# Heater.net
KiCad netlist of a schematic drawn in Altium Designer
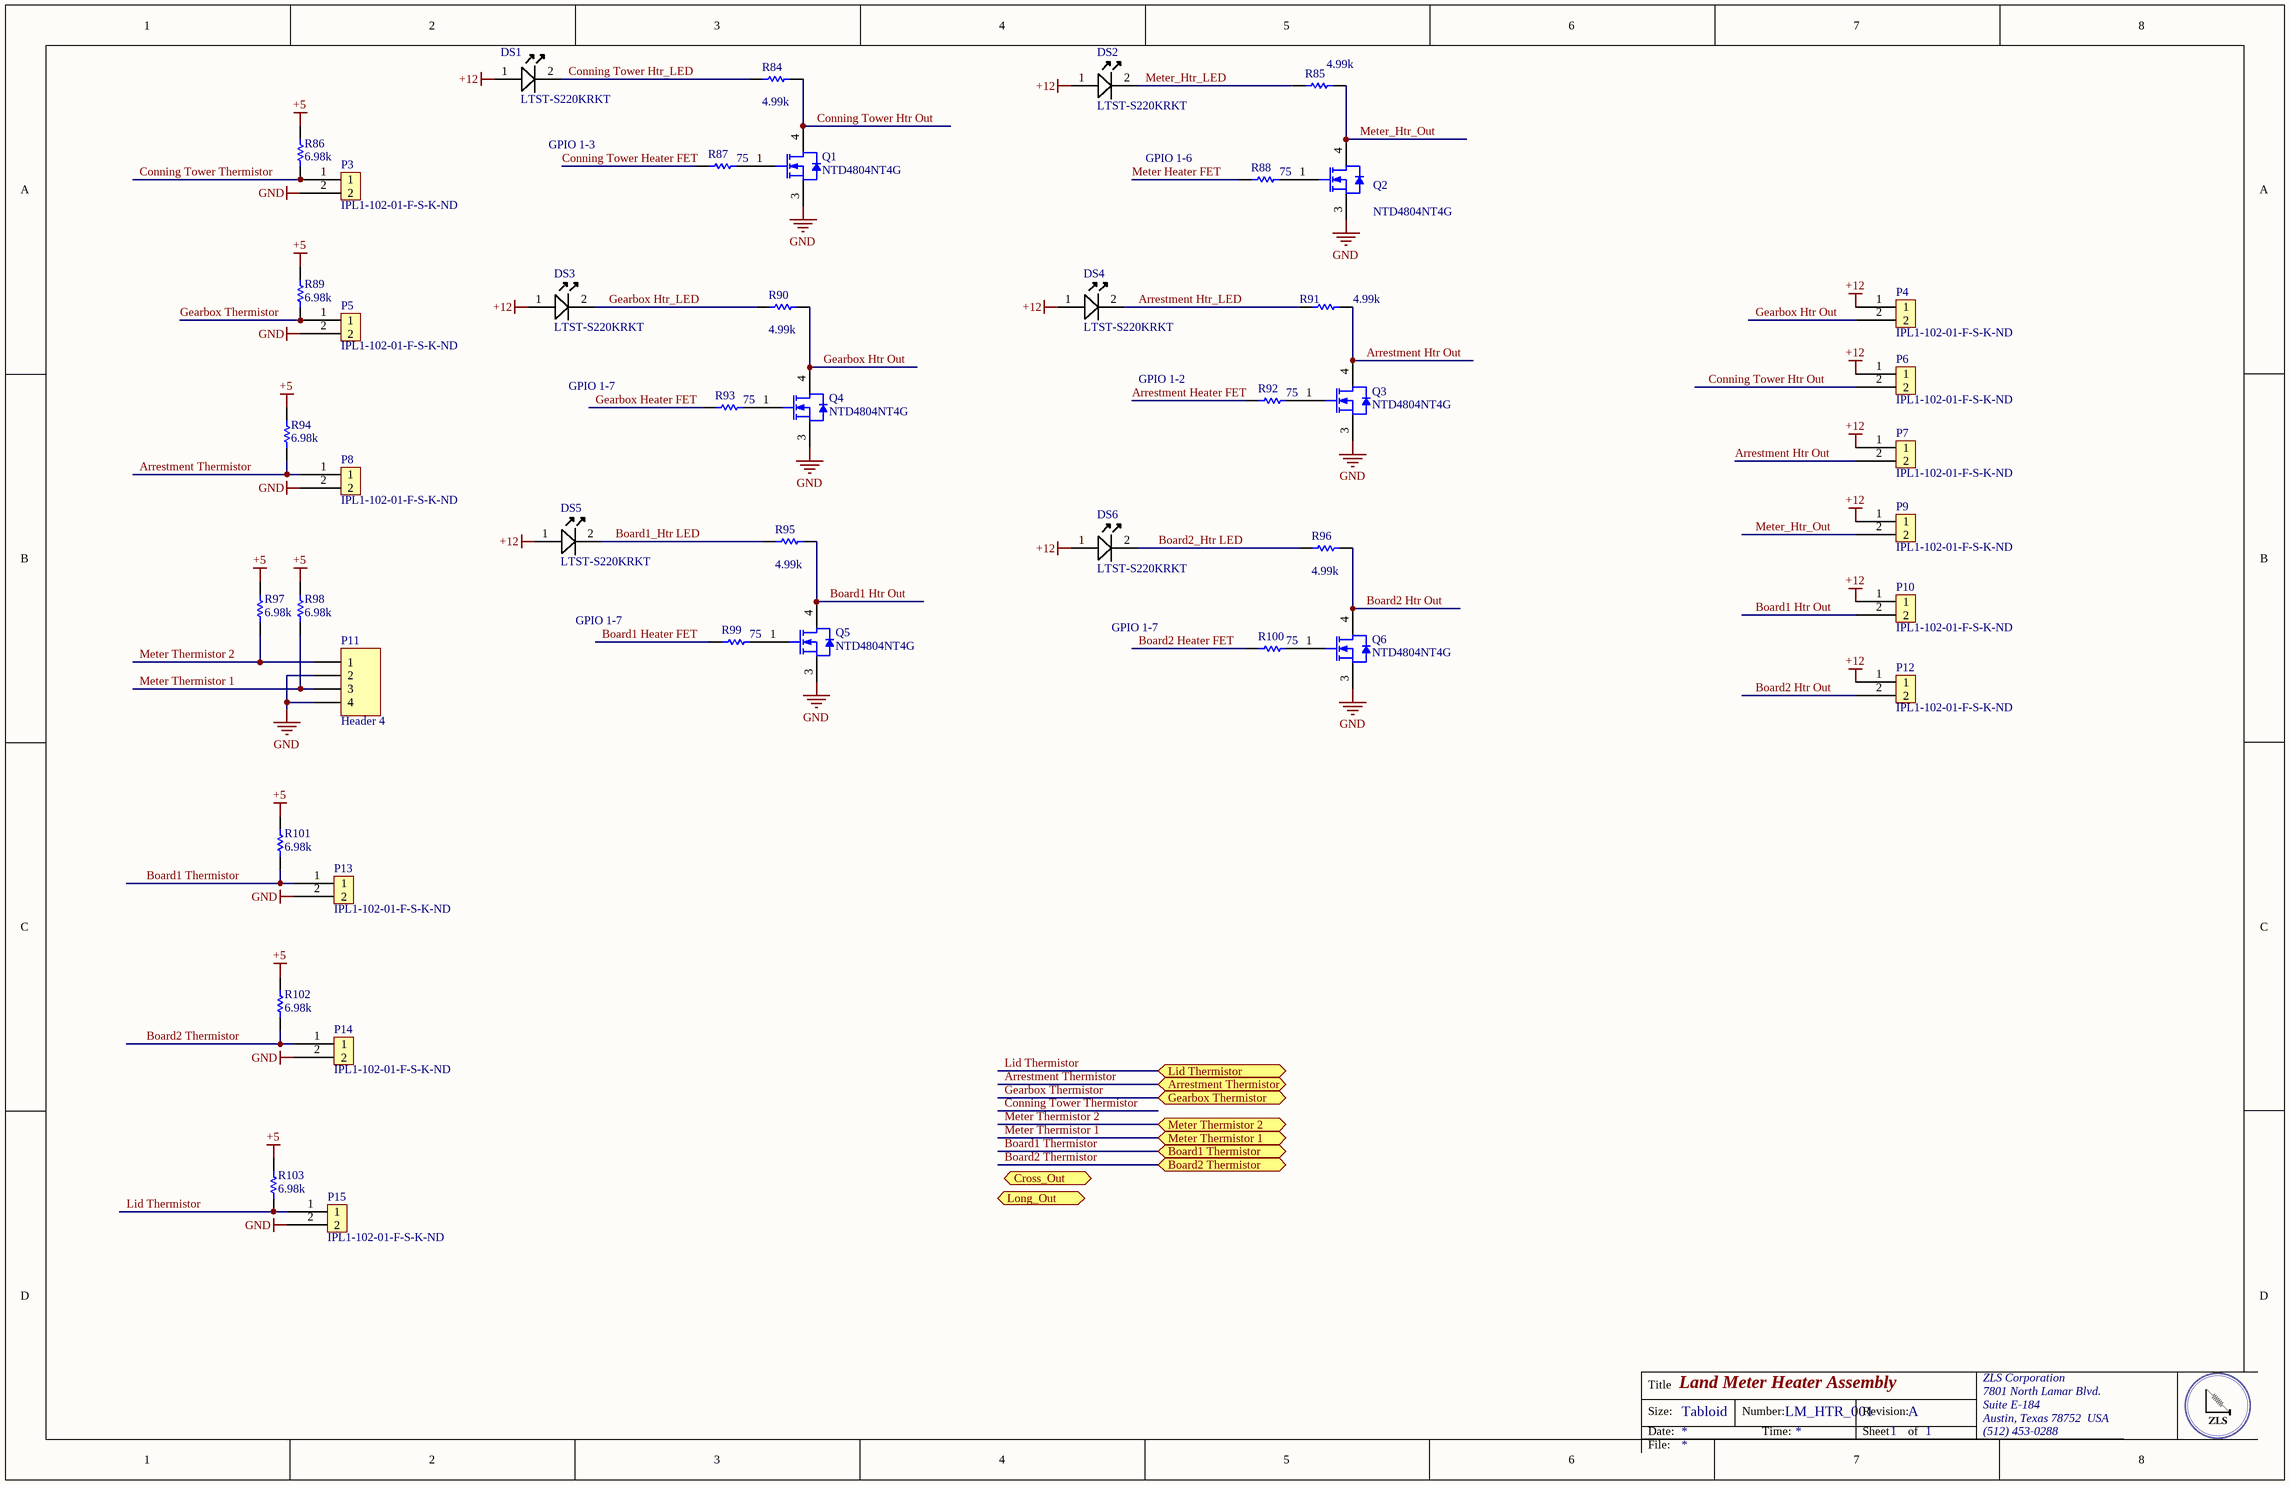
[diagram p0: Heater.SchDoc]

(export (version "E")
  (design (tool "Eeschema 10.0.6"))
  (components
    (comp (ref "DS1")
      (value "Visible Name Value Type    False Description Lite-On LTST-S220KRKT Red LED, 631 nm 2012 (0805) Side View, Rectangle Lens SMD package STRING")
      (footprint "0805C_L")
      (fields
        (field (name "MANUFACTURER") "Vishay / Lite-On")
        (field (name "MANUFACTURER PART NUMBER") "LTST-S220KRKT")
      )
      (libsource (lib "*") (part "LED A/K"))
    )
    (comp (ref "DS2")
      (value "Visible Name Value Type    False Description Lite-On LTST-S220KRKT Red LED, 631 nm 2012 (0805) Side View, Rectangle Lens SMD package STRING")
      (footprint "0805C_L")
      (fields
        (field (name "MANUFACTURER") "Vishay / Lite-On")
        (field (name "MANUFACTURER PART NUMBER") "LTST-S220KRKT")
      )
      (libsource (lib "*") (part "LED A/K"))
    )
    (comp (ref "DS3")
      (value "Visible Name Value Type    False Description Lite-On LTST-S220KRKT Red LED, 631 nm 2012 (0805) Side View, Rectangle Lens SMD package STRING")
      (footprint "0805C_L")
      (fields
        (field (name "MANUFACTURER") "Vishay / Lite-On")
        (field (name "MANUFACTURER PART NUMBER") "LTST-S220KRKT")
      )
      (libsource (lib "*") (part "LED A/K"))
    )
    (comp (ref "DS4")
      (value "Visible Name Value Type    False Description Lite-On LTST-S220KRKT Red LED, 631 nm 2012 (0805) Side View, Rectangle Lens SMD package STRING")
      (footprint "0805C_L")
      (fields
        (field (name "MANUFACTURER") "Vishay / Lite-On")
        (field (name "MANUFACTURER PART NUMBER") "LTST-S220KRKT")
      )
      (libsource (lib "*") (part "LED A/K"))
    )
    (comp (ref "DS5")
      (value "Visible Name Value Type    False Description Lite-On LTST-S220KRKT Red LED, 631 nm 2012 (0805) Side View, Rectangle Lens SMD package STRING")
      (footprint "0805C_L")
      (fields
        (field (name "MANUFACTURER") "Vishay / Lite-On")
        (field (name "MANUFACTURER PART NUMBER") "LTST-S220KRKT")
      )
      (libsource (lib "*") (part "LED A/K"))
    )
    (comp (ref "DS6")
      (value "Visible Name Value Type    False Description Lite-On LTST-S220KRKT Red LED, 631 nm 2012 (0805) Side View, Rectangle Lens SMD package STRING")
      (footprint "0805C_L")
      (fields
        (field (name "MANUFACTURER") "Vishay / Lite-On")
        (field (name "MANUFACTURER PART NUMBER") "LTST-S220KRKT")
      )
      (libsource (lib "*") (part "LED A/K"))
    )
    (comp (ref "P3")
      (value "IPL1-102-01-F-S-K")
      (footprint "IPL1-102-01-F-S-K")
      (description ".100 TERMINAL ASSEMBLY")
      (fields
        (field (name "SUPPLIER PART NUMBER 1") "IPL1-102-01-F-S-K-ND")
        (field (name "MANUFACTURER") "Samtec Inc.")
      )
      (libsource (lib "ZLS_Schematic_lib") (part "IPL1-102-01-F-S-K"))
    )
    (comp (ref "P4")
      (value "IPL1-102-01-F-S-K")
      (footprint "IPL1-102-01-F-S-K")
      (description ".100 TERMINAL ASSEMBLY")
      (fields
        (field (name "SUPPLIER PART NUMBER 1") "IPL1-102-01-F-S-K-ND")
        (field (name "MANUFACTURER") "Samtec Inc.")
      )
      (libsource (lib "ZLS_Schematic_lib") (part "IPL1-102-01-F-S-K"))
    )
    (comp (ref "P5")
      (value "IPL1-102-01-F-S-K")
      (footprint "IPL1-102-01-F-S-K")
      (description ".100 TERMINAL ASSEMBLY")
      (fields
        (field (name "SUPPLIER PART NUMBER 1") "IPL1-102-01-F-S-K-ND")
        (field (name "MANUFACTURER") "Samtec Inc.")
      )
      (libsource (lib "ZLS_Schematic_lib") (part "IPL1-102-01-F-S-K"))
    )
    (comp (ref "P6")
      (value "IPL1-102-01-F-S-K")
      (footprint "IPL1-102-01-F-S-K")
      (description ".100 TERMINAL ASSEMBLY")
      (fields
        (field (name "SUPPLIER PART NUMBER 1") "IPL1-102-01-F-S-K-ND")
        (field (name "MANUFACTURER") "Samtec Inc.")
      )
      (libsource (lib "ZLS_Schematic_lib") (part "IPL1-102-01-F-S-K"))
    )
    (comp (ref "P7")
      (value "IPL1-102-01-F-S-K")
      (footprint "IPL1-102-01-F-S-K")
      (description ".100 TERMINAL ASSEMBLY")
      (fields
        (field (name "SUPPLIER PART NUMBER 1") "IPL1-102-01-F-S-K-ND")
        (field (name "MANUFACTURER") "Samtec Inc.")
      )
      (libsource (lib "ZLS_Schematic_lib") (part "IPL1-102-01-F-S-K"))
    )
    (comp (ref "P8")
      (value "IPL1-102-01-F-S-K")
      (footprint "IPL1-102-01-F-S-K")
      (description ".100 TERMINAL ASSEMBLY")
      (fields
        (field (name "SUPPLIER PART NUMBER 1") "IPL1-102-01-F-S-K-ND")
        (field (name "MANUFACTURER") "Samtec Inc.")
      )
      (libsource (lib "ZLS_Schematic_lib") (part "IPL1-102-01-F-S-K"))
    )
    (comp (ref "P9")
      (value "IPL1-102-01-F-S-K")
      (footprint "IPL1-102-01-F-S-K")
      (description ".100 TERMINAL ASSEMBLY")
      (fields
        (field (name "SUPPLIER PART NUMBER 1") "IPL1-102-01-F-S-K-ND")
        (field (name "MANUFACTURER") "Samtec Inc.")
      )
      (libsource (lib "ZLS_Schematic_lib") (part "IPL1-102-01-F-S-K"))
    )
    (comp (ref "P10")
      (value "IPL1-102-01-F-S-K")
      (footprint "IPL1-102-01-F-S-K")
      (description ".100 TERMINAL ASSEMBLY")
      (fields
        (field (name "SUPPLIER PART NUMBER 1") "IPL1-102-01-F-S-K-ND")
        (field (name "MANUFACTURER") "Samtec Inc.")
      )
      (libsource (lib "ZLS_Schematic_lib") (part "IPL1-102-01-F-S-K"))
    )
    (comp (ref "P11")
      (value "Header 4")
      (footprint "IPL1-104-01-L-S-K")
      (description "Header, 4-Pin")
      (fields (field (name "PUBLISHER") "Altium Limited"))
      (libsource (lib "Miscellaneous Connectors") (part "Header 4"))
    )
    (comp (ref "P12")
      (value "IPL1-102-01-F-S-K")
      (footprint "IPL1-102-01-F-S-K")
      (description ".100 TERMINAL ASSEMBLY")
      (fields
        (field (name "SUPPLIER PART NUMBER 1") "IPL1-102-01-F-S-K-ND")
        (field (name "MANUFACTURER") "Samtec Inc.")
      )
      (libsource (lib "ZLS_Schematic_lib") (part "IPL1-102-01-F-S-K"))
    )
    (comp (ref "P13")
      (value "IPL1-102-01-F-S-K")
      (footprint "IPL1-102-01-F-S-K")
      (description ".100 TERMINAL ASSEMBLY")
      (fields
        (field (name "SUPPLIER PART NUMBER 1") "IPL1-102-01-F-S-K-ND")
        (field (name "MANUFACTURER") "Samtec Inc.")
      )
      (libsource (lib "ZLS_Schematic_lib") (part "IPL1-102-01-F-S-K"))
    )
    (comp (ref "P14")
      (value "IPL1-102-01-F-S-K")
      (footprint "IPL1-102-01-F-S-K")
      (description ".100 TERMINAL ASSEMBLY")
      (fields
        (field (name "SUPPLIER PART NUMBER 1") "IPL1-102-01-F-S-K-ND")
        (field (name "MANUFACTURER") "Samtec Inc.")
      )
      (libsource (lib "ZLS_Schematic_lib") (part "IPL1-102-01-F-S-K"))
    )
    (comp (ref "P15")
      (value "IPL1-102-01-F-S-K")
      (footprint "IPL1-102-01-F-S-K")
      (description ".100 TERMINAL ASSEMBLY")
      (fields
        (field (name "SUPPLIER PART NUMBER 1") "IPL1-102-01-F-S-K-ND")
        (field (name "MANUFACTURER") "Samtec Inc.")
      )
      (libsource (lib "ZLS_Schematic_lib") (part "IPL1-102-01-F-S-K"))
    )
    (comp (ref "Q1")
      (value "NTD4804NT4G")
      (footprint "ONSC-DPAK-3-369AA-01_V")
      (description "Power MOSFET, 30 V, 117 A, Single N-Channel, 3-Pin DPAK, Pb-Free, Tape and Reel")
      (fields (field (name "MANUFACTURER") "On Semiconductor"))
      (libsource (lib "Altium Content Vault") (part "CMP-1058-00341-1"))
    )
    (comp (ref "Q2")
      (value "NTD4804NT4G")
      (footprint "ONSC-DPAK-3-369AA-01_V")
      (description "Power MOSFET, 30 V, 117 A, Single N-Channel, 3-Pin DPAK, Pb-Free, Tape and Reel")
      (fields (field (name "MANUFACTURER") "On Semiconductor"))
      (libsource (lib "Altium Content Vault") (part "CMP-1058-00341-1"))
    )
    (comp (ref "Q3")
      (value "NTD4804NT4G")
      (footprint "ONSC-DPAK-3-369AA-01_V")
      (description "Power MOSFET, 30 V, 117 A, Single N-Channel, 3-Pin DPAK, Pb-Free, Tape and Reel")
      (fields (field (name "MANUFACTURER") "On Semiconductor"))
      (libsource (lib "Altium Content Vault") (part "CMP-1058-00341-1"))
    )
    (comp (ref "Q4")
      (value "NTD4804NT4G")
      (footprint "ONSC-DPAK-3-369AA-01_V")
      (description "Power MOSFET, 30 V, 117 A, Single N-Channel, 3-Pin DPAK, Pb-Free, Tape and Reel")
      (fields (field (name "MANUFACTURER") "On Semiconductor"))
      (libsource (lib "Altium Content Vault") (part "CMP-1058-00341-1"))
    )
    (comp (ref "Q5")
      (value "NTD4804NT4G")
      (footprint "ONSC-DPAK-3-369AA-01_V")
      (description "Power MOSFET, 30 V, 117 A, Single N-Channel, 3-Pin DPAK, Pb-Free, Tape and Reel")
      (fields (field (name "MANUFACTURER") "On Semiconductor"))
      (libsource (lib "Altium Content Vault") (part "CMP-1058-00341-1"))
    )
    (comp (ref "Q6")
      (value "NTD4804NT4G")
      (footprint "ONSC-DPAK-3-369AA-01_V")
      (description "Power MOSFET, 30 V, 117 A, Single N-Channel, 3-Pin DPAK, Pb-Free, Tape and Reel")
      (fields (field (name "MANUFACTURER") "On Semiconductor"))
      (libsource (lib "Altium Content Vault") (part "CMP-1058-00341-1"))
    )
    (comp (ref "R84")
      (value "~")
      (footprint "RESC0805(2012)_L")
      (fields
        (field (name "MANUFACTURER") "Vishay Dale")
        (field (name "MANUFACTURER PART NUMBER") "CRCW08054K99FKEA")
        (field (name "RESISTANCE (OHMS)") "4.99k")
        (field (name "TOLERANCE") "±1%")
      )
      (libsource (lib "Altium Content Vault") (part "CMP-1013-00393-1"))
    )
    (comp (ref "R85")
      (value "~")
      (footprint "RESC0805(2012)_L")
      (fields
        (field (name "MANUFACTURER") "Vishay Dale")
        (field (name "MANUFACTURER PART NUMBER") "CRCW08054K99FKEA")
        (field (name "RESISTANCE (OHMS)") "4.99k")
        (field (name "TOLERANCE") "±1%")
      )
      (libsource (lib "Altium Content Vault") (part "CMP-1013-00393-1"))
    )
    (comp (ref "R86")
      (value "6K98 1% 0805(2012)")
      (footprint "RESC0805(2012)_N")
      (description "6K98 0.125W 1% 0805 (2012 Metric)  SMD")
      (fields
        (field (name "MANUFACTURER") "Vishay Dale")
        (field (name "MANUFACTURER PART NUMBER") "CRCW08056K98FKEA")
        (field (name "RESISTANCE (OHMS)") "6.98k")
      )
      (libsource (lib "Altium Content Vault") (part "CMP-1013-00606-1"))
    )
    (comp (ref "R87")
      (value "~")
      (footprint "RESC0805(2012)_L")
      (fields
        (field (name "MANUFACTURER") "Vishay Dale")
        (field (name "MANUFACTURER PART NUMBER") "CRCW080575R0FKEA")
        (field (name "RESISTANCE (OHMS)") "75")
        (field (name "TOLERANCE") "±1%")
      )
      (libsource (lib "Altium Content Vault") (part "CMP-1013-00393-1"))
    )
    (comp (ref "R88")
      (value "~")
      (footprint "RESC0805(2012)_L")
      (fields
        (field (name "MANUFACTURER") "Vishay Dale")
        (field (name "MANUFACTURER PART NUMBER") "CRCW080575R0FKEA")
        (field (name "RESISTANCE (OHMS)") "75")
        (field (name "TOLERANCE") "±1%")
      )
      (libsource (lib "Altium Content Vault") (part "CMP-1013-00393-1"))
    )
    (comp (ref "R89")
      (value "6K98 1% 0805(2012)")
      (footprint "RESC0805(2012)_N")
      (description "6K98 0.125W 1% 0805 (2012 Metric)  SMD")
      (fields
        (field (name "MANUFACTURER") "Vishay Dale")
        (field (name "MANUFACTURER PART NUMBER") "CRCW08056K98FKEA")
        (field (name "RESISTANCE (OHMS)") "6.98k")
      )
      (libsource (lib "Altium Content Vault") (part "CMP-1013-00606-1"))
    )
    (comp (ref "R90")
      (value "~")
      (footprint "RESC0805(2012)_L")
      (fields
        (field (name "MANUFACTURER") "Vishay Dale")
        (field (name "MANUFACTURER PART NUMBER") "CRCW08054K99FKEA")
        (field (name "RESISTANCE (OHMS)") "4.99k")
        (field (name "TOLERANCE") "±1%")
      )
      (libsource (lib "Altium Content Vault") (part "CMP-1013-00393-1"))
    )
    (comp (ref "R91")
      (value "~")
      (footprint "RESC0805(2012)_L")
      (fields
        (field (name "MANUFACTURER") "Vishay Dale")
        (field (name "MANUFACTURER PART NUMBER") "CRCW08054K99FKEA")
        (field (name "RESISTANCE (OHMS)") "4.99k")
        (field (name "TOLERANCE") "±1%")
      )
      (libsource (lib "Altium Content Vault") (part "CMP-1013-00393-1"))
    )
    (comp (ref "R92")
      (value "~")
      (footprint "RESC0805(2012)_L")
      (fields
        (field (name "MANUFACTURER") "Vishay Dale")
        (field (name "MANUFACTURER PART NUMBER") "CRCW080575R0FKEA")
        (field (name "RESISTANCE (OHMS)") "75")
        (field (name "TOLERANCE") "±1%")
      )
      (libsource (lib "Altium Content Vault") (part "CMP-1013-00393-1"))
    )
    (comp (ref "R93")
      (value "~")
      (footprint "RESC0805(2012)_L")
      (fields
        (field (name "MANUFACTURER") "Vishay Dale")
        (field (name "MANUFACTURER PART NUMBER") "CRCW080575R0FKEA")
        (field (name "RESISTANCE (OHMS)") "75")
        (field (name "TOLERANCE") "±1%")
      )
      (libsource (lib "Altium Content Vault") (part "CMP-1013-00393-1"))
    )
    (comp (ref "R94")
      (value "6K98 1% 0805(2012)")
      (footprint "RESC0805(2012)_N")
      (description "6K98 0.125W 1% 0805 (2012 Metric)  SMD")
      (fields
        (field (name "MANUFACTURER") "Vishay Dale")
        (field (name "MANUFACTURER PART NUMBER") "CRCW08056K98FKEA")
        (field (name "RESISTANCE (OHMS)") "6.98k")
      )
      (libsource (lib "Altium Content Vault") (part "CMP-1013-00606-1"))
    )
    (comp (ref "R95")
      (value "~")
      (footprint "RESC0805(2012)_L")
      (fields
        (field (name "MANUFACTURER") "Vishay Dale")
        (field (name "MANUFACTURER PART NUMBER") "CRCW08054K99FKEA")
        (field (name "RESISTANCE (OHMS)") "4.99k")
        (field (name "TOLERANCE") "±1%")
      )
      (libsource (lib "Altium Content Vault") (part "CMP-1013-00393-1"))
    )
    (comp (ref "R96")
      (value "~")
      (footprint "RESC0805(2012)_L")
      (fields
        (field (name "MANUFACTURER") "Vishay Dale")
        (field (name "MANUFACTURER PART NUMBER") "CRCW08054K99FKEA")
        (field (name "RESISTANCE (OHMS)") "4.99k")
        (field (name "TOLERANCE") "±1%")
      )
      (libsource (lib "Altium Content Vault") (part "CMP-1013-00393-1"))
    )
    (comp (ref "R97")
      (value "6K98 1% 0805(2012)")
      (footprint "RESC0805(2012)_N")
      (description "6K98 0.125W 1% 0805 (2012 Metric)  SMD")
      (fields
        (field (name "MANUFACTURER") "Vishay Dale")
        (field (name "MANUFACTURER PART NUMBER") "CRCW08056K98FKEA")
        (field (name "RESISTANCE (OHMS)") "6.98k")
      )
      (libsource (lib "Altium Content Vault") (part "CMP-1013-00606-1"))
    )
    (comp (ref "R98")
      (value "6K98 1% 0805(2012)")
      (footprint "RESC0805(2012)_N")
      (description "6K98 0.125W 1% 0805 (2012 Metric)  SMD")
      (fields
        (field (name "MANUFACTURER") "Vishay Dale")
        (field (name "MANUFACTURER PART NUMBER") "CRCW08056K98FKEA")
        (field (name "RESISTANCE (OHMS)") "6.98k")
      )
      (libsource (lib "Altium Content Vault") (part "CMP-1013-00606-1"))
    )
    (comp (ref "R99")
      (value "~")
      (footprint "RESC0805(2012)_L")
      (fields
        (field (name "MANUFACTURER") "Vishay Dale")
        (field (name "MANUFACTURER PART NUMBER") "CRCW080575R0FKEA")
        (field (name "RESISTANCE (OHMS)") "75")
        (field (name "TOLERANCE") "±1%")
      )
      (libsource (lib "Altium Content Vault") (part "CMP-1013-00393-1"))
    )
    (comp (ref "R100")
      (value "~")
      (footprint "RESC0805(2012)_L")
      (fields
        (field (name "MANUFACTURER") "Vishay Dale")
        (field (name "MANUFACTURER PART NUMBER") "CRCW080575R0FKEA")
        (field (name "RESISTANCE (OHMS)") "75")
        (field (name "TOLERANCE") "±1%")
      )
      (libsource (lib "Altium Content Vault") (part "CMP-1013-00393-1"))
    )
    (comp (ref "R101")
      (value "6K98 1% 0805(2012)")
      (footprint "RESC0805(2012)_N")
      (description "6K98 0.125W 1% 0805 (2012 Metric)  SMD")
      (fields
        (field (name "MANUFACTURER") "Vishay Dale")
        (field (name "MANUFACTURER PART NUMBER") "CRCW08056K98FKEA")
        (field (name "RESISTANCE (OHMS)") "6.98k")
      )
      (libsource (lib "Altium Content Vault") (part "CMP-1013-00606-1"))
    )
    (comp (ref "R102")
      (value "6K98 1% 0805(2012)")
      (footprint "RESC0805(2012)_N")
      (description "6K98 0.125W 1% 0805 (2012 Metric)  SMD")
      (fields
        (field (name "MANUFACTURER") "Vishay Dale")
        (field (name "MANUFACTURER PART NUMBER") "CRCW08056K98FKEA")
        (field (name "RESISTANCE (OHMS)") "6.98k")
      )
      (libsource (lib "Altium Content Vault") (part "CMP-1013-00606-1"))
    )
    (comp (ref "R103")
      (value "6K98 1% 0805(2012)")
      (footprint "RESC0805(2012)_N")
      (description "6K98 0.125W 1% 0805 (2012 Metric)  SMD")
      (fields
        (field (name "MANUFACTURER") "Vishay Dale")
        (field (name "MANUFACTURER PART NUMBER") "CRCW08056K98FKEA")
        (field (name "RESISTANCE (OHMS)") "6.98k")
      )
      (libsource (lib "Altium Content Vault") (part "CMP-1013-00606-1"))
    )
  )
  (nets
    (net (code "1") (name "+5") (class "Default")
      (node (ref "R101") (pin "1") (pinfunction "1_1") (pintype "passive"))
      (node (ref "R102") (pin "1") (pinfunction "1_1") (pintype "passive"))
      (node (ref "R103") (pin "1") (pinfunction "1_1") (pintype "passive"))
      (node (ref "R86") (pin "2") (pinfunction "2_2") (pintype "passive"))
      (node (ref "R89") (pin "2") (pinfunction "2_2") (pintype "passive"))
      (node (ref "R94") (pin "1") (pinfunction "1_1") (pintype "passive"))
      (node (ref "R97") (pin "1") (pinfunction "1_1") (pintype "passive"))
      (node (ref "R98") (pin "2") (pinfunction "2_2") (pintype "passive"))
    )
    (net (code "2") (name "+12") (class "Default")
      (node (ref "DS1") (pin "1") (pinfunction "A_1") (pintype "passive"))
      (node (ref "DS2") (pin "1") (pinfunction "A_1") (pintype "passive"))
      (node (ref "DS3") (pin "1") (pinfunction "A_1") (pintype "passive"))
      (node (ref "DS4") (pin "1") (pinfunction "A_1") (pintype "passive"))
      (node (ref "DS5") (pin "1") (pinfunction "A_1") (pintype "passive"))
      (node (ref "DS6") (pin "1") (pinfunction "A_1") (pintype "passive"))
      (node (ref "P10") (pin "1") (pinfunction "1_1") (pintype "passive"))
      (node (ref "P12") (pin "1") (pinfunction "1_1") (pintype "passive"))
      (node (ref "P4") (pin "1") (pinfunction "1_1") (pintype "passive"))
      (node (ref "P6") (pin "1") (pinfunction "1_1") (pintype "passive"))
      (node (ref "P7") (pin "1") (pinfunction "1_1") (pintype "passive"))
      (node (ref "P9") (pin "1") (pinfunction "1_1") (pintype "passive"))
    )
    (net (code "3") (name "/Arrestment Heater FET") (class "Default")
      (node (ref "R92") (pin "1") (pinfunction "1_1") (pintype "passive"))
    )
    (net (code "4") (name "/Arrestment Htr Out") (class "Default")
      (node (ref "P7") (pin "2") (pinfunction "2_2") (pintype "passive"))
      (node (ref "Q3") (pin "4") (pinfunction "D_4") (pintype "passive"))
      (node (ref "R91") (pin "2") (pinfunction "2_2") (pintype "passive"))
    )
    (net (code "5") (name "/Arrestment Htr_LED") (class "Default")
      (node (ref "DS4") (pin "2") (pinfunction "K_2") (pintype "passive"))
      (node (ref "R91") (pin "1") (pinfunction "1_1") (pintype "passive"))
    )
    (net (code "6") (name "/Arrestment Thermistor") (class "Default")
      (node (ref "P8") (pin "1") (pinfunction "1_1") (pintype "passive"))
      (node (ref "R94") (pin "2") (pinfunction "2_2") (pintype "passive"))
    )
    (net (code "7") (name "/Board1 Heater FET") (class "Default")
      (node (ref "R99") (pin "1") (pinfunction "1_1") (pintype "passive"))
    )
    (net (code "8") (name "/Board1 Htr Out") (class "Default")
      (node (ref "P10") (pin "2") (pinfunction "2_2") (pintype "passive"))
      (node (ref "Q5") (pin "4") (pinfunction "D_4") (pintype "passive"))
      (node (ref "R95") (pin "1") (pinfunction "1_1") (pintype "passive"))
    )
    (net (code "9") (name "/Board1 Thermistor") (class "Default")
      (node (ref "P13") (pin "1") (pinfunction "1_1") (pintype "passive"))
      (node (ref "R101") (pin "2") (pinfunction "2_2") (pintype "passive"))
    )
    (net (code "10") (name "/Board1_Htr LED") (class "Default")
      (node (ref "DS5") (pin "2") (pinfunction "K_2") (pintype "passive"))
      (node (ref "R95") (pin "2") (pinfunction "2_2") (pintype "passive"))
    )
    (net (code "11") (name "/Board2 Heater FET") (class "Default")
      (node (ref "R100") (pin "1") (pinfunction "1_1") (pintype "passive"))
    )
    (net (code "12") (name "/Board2 Htr Out") (class "Default")
      (node (ref "P12") (pin "2") (pinfunction "2_2") (pintype "passive"))
      (node (ref "Q6") (pin "4") (pinfunction "D_4") (pintype "passive"))
      (node (ref "R96") (pin "1") (pinfunction "1_1") (pintype "passive"))
    )
    (net (code "13") (name "/Board2 Thermistor") (class "Default")
      (node (ref "P14") (pin "1") (pinfunction "1_1") (pintype "passive"))
      (node (ref "R102") (pin "2") (pinfunction "2_2") (pintype "passive"))
    )
    (net (code "14") (name "/Board2_Htr LED") (class "Default")
      (node (ref "DS6") (pin "2") (pinfunction "K_2") (pintype "passive"))
      (node (ref "R96") (pin "2") (pinfunction "2_2") (pintype "passive"))
    )
    (net (code "15") (name "/Conning Tower Heater FET") (class "Default")
      (node (ref "R87") (pin "1") (pinfunction "1_1") (pintype "passive"))
    )
    (net (code "16") (name "/Conning Tower Htr Out") (class "Default")
      (node (ref "P6") (pin "2") (pinfunction "2_2") (pintype "passive"))
      (node (ref "Q1") (pin "4") (pinfunction "D_4") (pintype "passive"))
      (node (ref "R84") (pin "1") (pinfunction "1_1") (pintype "passive"))
    )
    (net (code "17") (name "/Conning Tower Htr_LED") (class "Default")
      (node (ref "DS1") (pin "2") (pinfunction "K_2") (pintype "passive"))
      (node (ref "R84") (pin "2") (pinfunction "2_2") (pintype "passive"))
    )
    (net (code "18") (name "/Conning Tower Thermistor") (class "Default")
      (node (ref "P3") (pin "1") (pinfunction "1_1") (pintype "passive"))
      (node (ref "R86") (pin "1") (pinfunction "1_1") (pintype "passive"))
    )
    (net (code "20") (name "/Gearbox Heater FET") (class "Default")
      (node (ref "R93") (pin "1") (pinfunction "1_1") (pintype "passive"))
    )
    (net (code "21") (name "/Gearbox Htr Out") (class "Default")
      (node (ref "P4") (pin "2") (pinfunction "2_2") (pintype "passive"))
      (node (ref "Q4") (pin "4") (pinfunction "D_4") (pintype "passive"))
      (node (ref "R90") (pin "1") (pinfunction "1_1") (pintype "passive"))
    )
    (net (code "22") (name "/Gearbox Htr_LED") (class "Default")
      (node (ref "DS3") (pin "2") (pinfunction "K_2") (pintype "passive"))
      (node (ref "R90") (pin "2") (pinfunction "2_2") (pintype "passive"))
    )
    (net (code "23") (name "/Gearbox Thermistor") (class "Default")
      (node (ref "P5") (pin "1") (pinfunction "1_1") (pintype "passive"))
      (node (ref "R89") (pin "1") (pinfunction "1_1") (pintype "passive"))
    )
    (net (code "24") (name "/Lid Thermistor") (class "Default")
      (node (ref "P15") (pin "1") (pinfunction "1_1") (pintype "passive"))
      (node (ref "R103") (pin "2") (pinfunction "2_2") (pintype "passive"))
    )
    (net (code "26") (name "/Meter Heater FET") (class "Default")
      (node (ref "R88") (pin "1") (pinfunction "1_1") (pintype "passive"))
    )
    (net (code "27") (name "/Meter Thermistor 1") (class "Default")
      (node (ref "P11") (pin "3") (pinfunction "3_3") (pintype "passive"))
      (node (ref "R98") (pin "1") (pinfunction "1_1") (pintype "passive"))
    )
    (net (code "28") (name "/Meter Thermistor 2") (class "Default")
      (node (ref "P11") (pin "1") (pinfunction "1_1") (pintype "passive"))
      (node (ref "R97") (pin "2") (pinfunction "2_2") (pintype "passive"))
    )
    (net (code "29") (name "/Meter_Htr_LED") (class "Default")
      (node (ref "DS2") (pin "2") (pinfunction "K_2") (pintype "passive"))
      (node (ref "R85") (pin "1") (pinfunction "1_1") (pintype "passive"))
    )
    (net (code "30") (name "/Meter_Htr_Out") (class "Default")
      (node (ref "P9") (pin "2") (pinfunction "2_2") (pintype "passive"))
      (node (ref "Q2") (pin "4") (pinfunction "D_4") (pintype "passive"))
      (node (ref "R85") (pin "2") (pinfunction "2_2") (pintype "passive"))
    )
    (net (code "31") (name "GND") (class "Default")
      (node (ref "P11") (pin "2") (pinfunction "2_2") (pintype "passive"))
      (node (ref "P11") (pin "4") (pinfunction "4_4") (pintype "passive"))
      (node (ref "P13") (pin "2") (pinfunction "2_2") (pintype "passive"))
      (node (ref "P14") (pin "2") (pinfunction "2_2") (pintype "passive"))
      (node (ref "P15") (pin "2") (pinfunction "2_2") (pintype "passive"))
      (node (ref "P3") (pin "2") (pinfunction "2_2") (pintype "passive"))
      (node (ref "P5") (pin "2") (pinfunction "2_2") (pintype "passive"))
      (node (ref "P8") (pin "2") (pinfunction "2_2") (pintype "passive"))
      (node (ref "Q1") (pin "3") (pinfunction "S_3") (pintype "passive"))
      (node (ref "Q2") (pin "3") (pinfunction "S_3") (pintype "passive"))
      (node (ref "Q3") (pin "3") (pinfunction "S_3") (pintype "passive"))
      (node (ref "Q4") (pin "3") (pinfunction "S_3") (pintype "passive"))
      (node (ref "Q5") (pin "3") (pinfunction "S_3") (pintype "passive"))
      (node (ref "Q6") (pin "3") (pinfunction "S_3") (pintype "passive"))
    )
    (net (code "32") (name "Net-(Q1-G)") (class "Default")
      (node (ref "Q1") (pin "1") (pinfunction "G_1") (pintype "passive"))
      (node (ref "R87") (pin "2") (pinfunction "2_2") (pintype "passive"))
    )
    (net (code "33") (name "Net-(Q2-G)") (class "Default")
      (node (ref "Q2") (pin "1") (pinfunction "G_1") (pintype "passive"))
      (node (ref "R88") (pin "2") (pinfunction "2_2") (pintype "passive"))
    )
    (net (code "34") (name "Net-(Q3-G)") (class "Default")
      (node (ref "Q3") (pin "1") (pinfunction "G_1") (pintype "passive"))
      (node (ref "R92") (pin "2") (pinfunction "2_2") (pintype "passive"))
    )
    (net (code "35") (name "Net-(Q4-G)") (class "Default")
      (node (ref "Q4") (pin "1") (pinfunction "G_1") (pintype "passive"))
      (node (ref "R93") (pin "2") (pinfunction "2_2") (pintype "passive"))
    )
    (net (code "36") (name "Net-(Q5-G)") (class "Default")
      (node (ref "Q5") (pin "1") (pinfunction "G_1") (pintype "passive"))
      (node (ref "R99") (pin "2") (pinfunction "2_2") (pintype "passive"))
    )
    (net (code "37") (name "Net-(Q6-G)") (class "Default")
      (node (ref "Q6") (pin "1") (pinfunction "G_1") (pintype "passive"))
      (node (ref "R100") (pin "2") (pinfunction "2_2") (pintype "passive"))
    )
  )
)
